# sequencer_uC.net
KiCad netlist of a schematic drawn in EAGLE
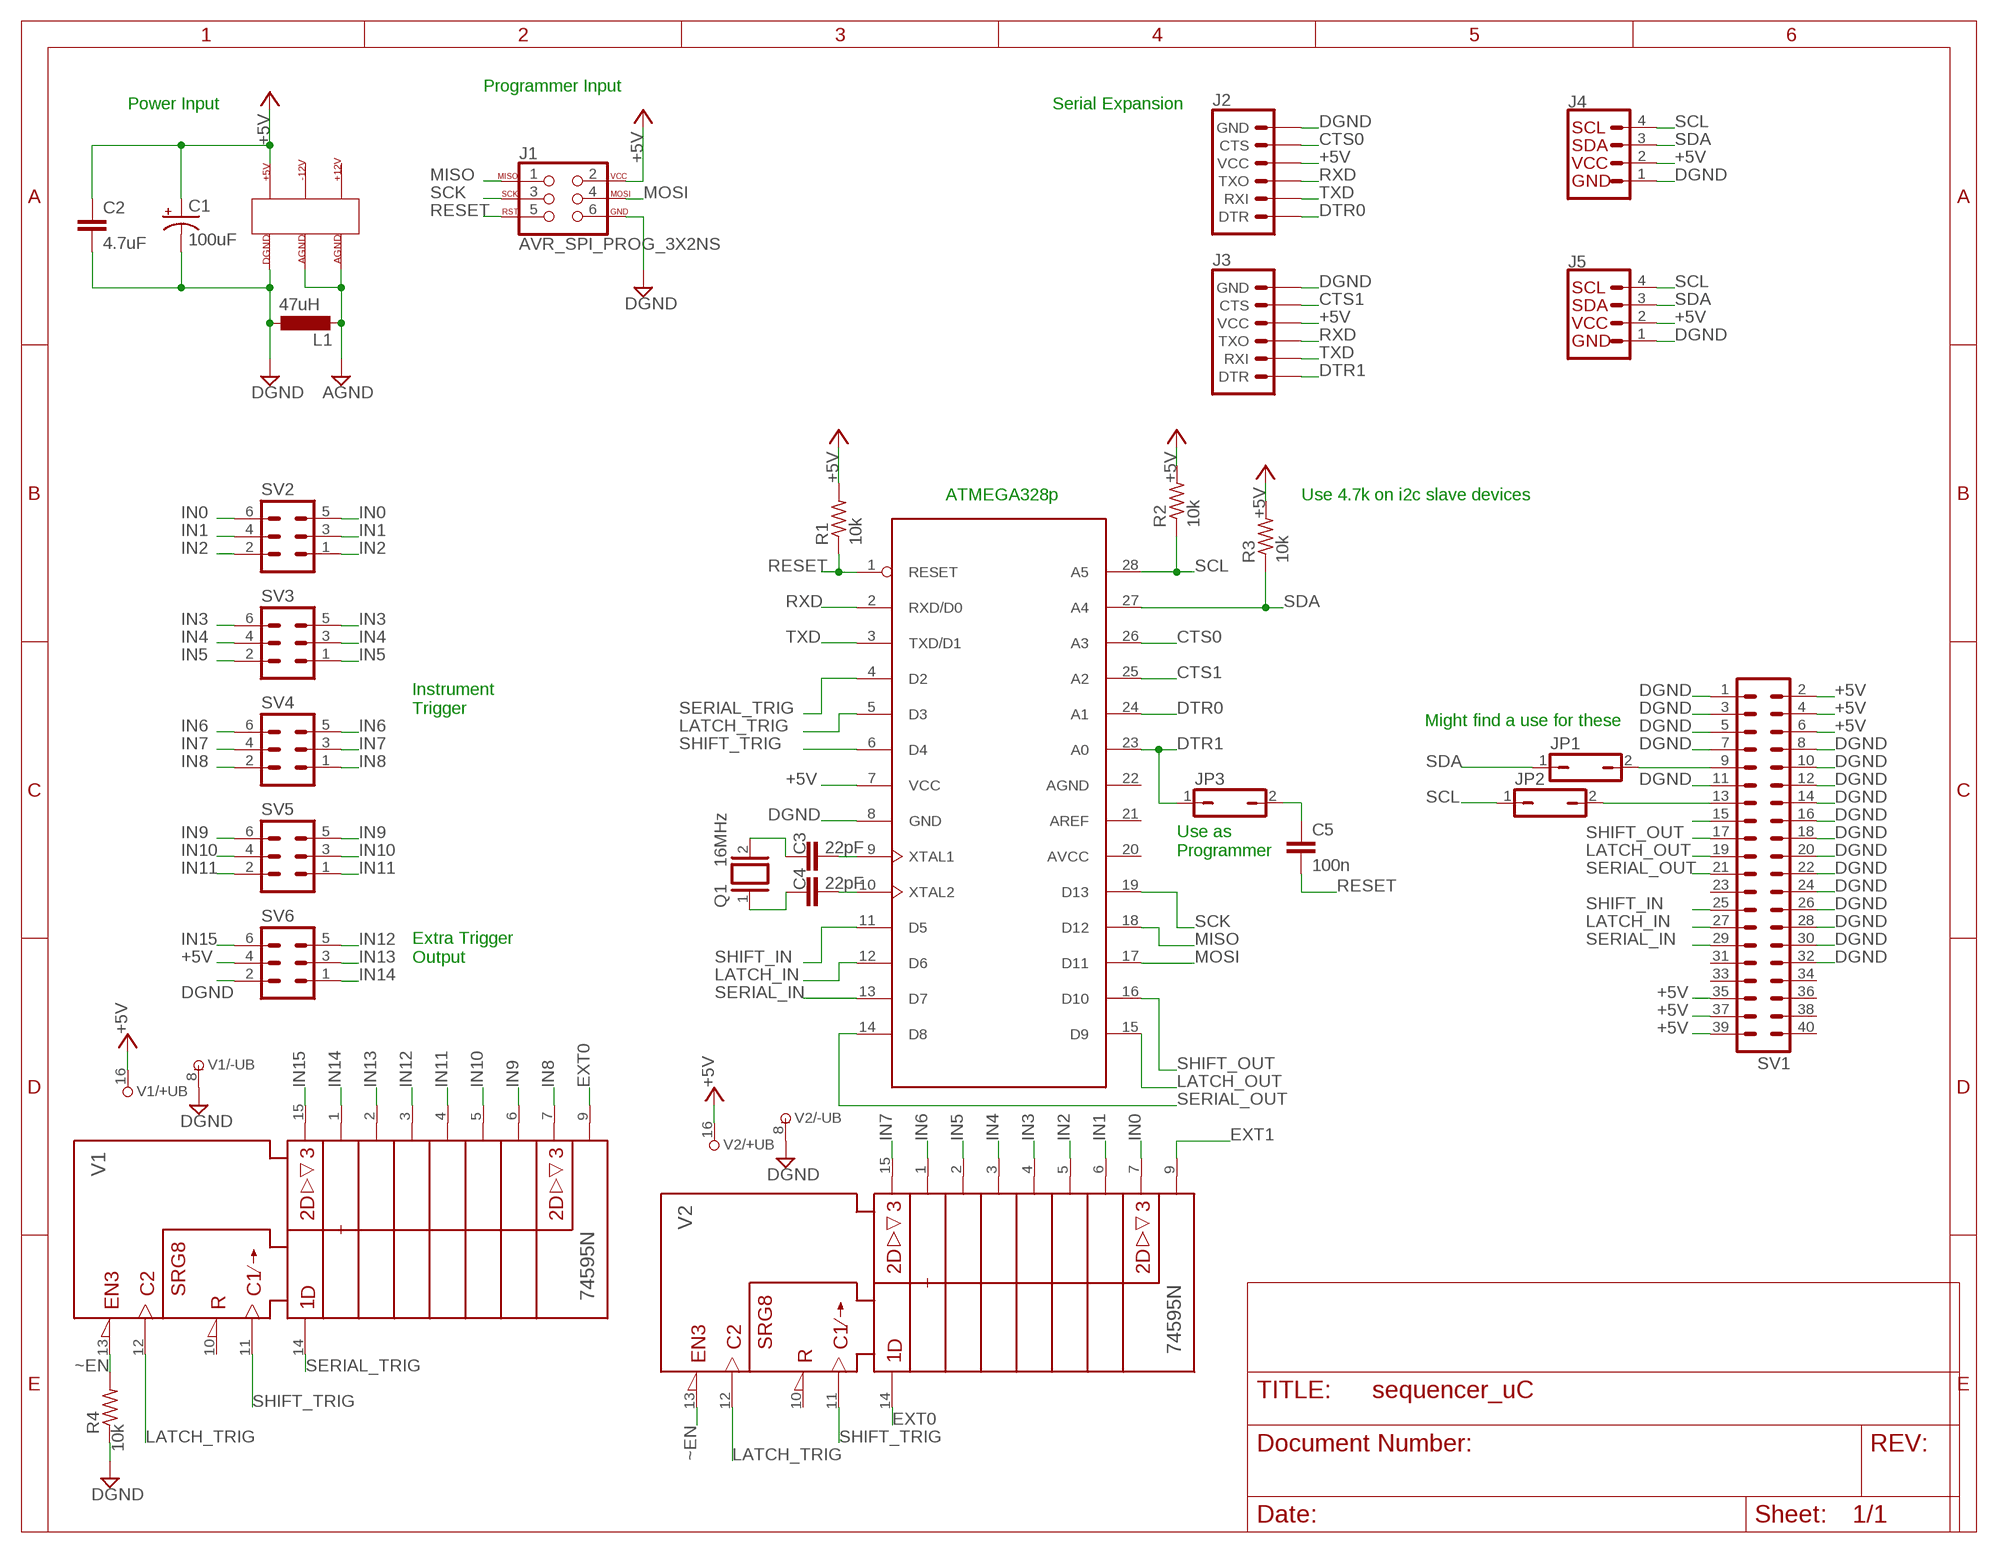
[diagram p0: schematic, sheet 1]

(export (version "E")
  (design (tool "Eeschema 10.0.6"))
  (components
    (comp (ref "AT1")
      (value "ATMEGA328")
      (footprint "eagle-import:DIP28-0.3IN")
      (libsource (lib "eagle-import") (part "ATMEGA328"))
    )
    (comp (ref "C1")
      (value "100uF")
      (footprint "eagle-import:E5-8,5")
      (libsource (lib "eagle-import") (part "CPOL-USE5-8.5"))
    )
    (comp (ref "C2")
      (value "4.7uF")
      (footprint "eagle-import:C050-024X044")
      (libsource (lib "eagle-import") (part "C-EU050-024X044"))
    )
    (comp (ref "C3")
      (value "22pF")
      (footprint "eagle-import:C050-024X044")
      (libsource (lib "eagle-import") (part "C-EU050-024X044"))
    )
    (comp (ref "C4")
      (value "22pF")
      (footprint "eagle-import:C050-024X044")
      (libsource (lib "eagle-import") (part "C-EU050-024X044"))
    )
    (comp (ref "C5")
      (value "100n")
      (footprint "eagle-import:C050-024X044")
      (libsource (lib "eagle-import") (part "C-EU050-024X044"))
    )
    (comp (ref "J1")
      (value "AVR_SPI_PROG_3X2NS")
      (footprint "eagle-import:2X3-NS")
      (libsource (lib "eagle-import") (part "AVR_SPI_PROG_3X2NS"))
    )
    (comp (ref "J2")
      (value "6_PIN_SERIAL_TARGETLONGPADS")
      (footprint "eagle-import:1X06_LONGPADS")
      (libsource (lib "eagle-import") (part "6_PIN_SERIAL_TARGETLONGPADS"))
    )
    (comp (ref "J3")
      (value "6_PIN_SERIAL_TARGETLONGPADS")
      (footprint "eagle-import:1X06_LONGPADS")
      (libsource (lib "eagle-import") (part "6_PIN_SERIAL_TARGETLONGPADS"))
    )
    (comp (ref "J4")
      (value "I2C_STANDARD")
      (footprint "eagle-import:1X04")
      (libsource (lib "eagle-import") (part "I2C_STANDARD"))
    )
    (comp (ref "J5")
      (value "I2C_STANDARD")
      (footprint "eagle-import:1X04")
      (libsource (lib "eagle-import") (part "I2C_STANDARD"))
    )
    (comp (ref "JP1")
      (value "JP1Q")
      (footprint "eagle-import:JP1")
      (libsource (lib "eagle-import") (part "JP1Q"))
    )
    (comp (ref "JP2")
      (value "JP1Q")
      (footprint "eagle-import:JP1")
      (libsource (lib "eagle-import") (part "JP1Q"))
    )
    (comp (ref "JP3")
      (value "JP1Q")
      (footprint "eagle-import:JP1")
      (libsource (lib "eagle-import") (part "JP1Q"))
    )
    (comp (ref "L1")
      (value "47uH")
      (footprint "eagle-import:0207_10")
      (libsource (lib "eagle-import") (part "L-EU0207/10"))
    )
    (comp (ref "Q1")
      (value "16MHz")
      (footprint "eagle-import:QS")
      (libsource (lib "eagle-import") (part "XTAL/S"))
    )
    (comp (ref "R1")
      (value "10k")
      (footprint "eagle-import:0204_7")
      (libsource (lib "eagle-import") (part "resistor_348_R-US_0204/7"))
    )
    (comp (ref "R2")
      (value "10k")
      (footprint "eagle-import:0204_7")
      (libsource (lib "eagle-import") (part "R-US_0204/7"))
    )
    (comp (ref "R3")
      (value "10k")
      (footprint "eagle-import:0204_7")
      (libsource (lib "eagle-import") (part "R-US_0204/7"))
    )
    (comp (ref "R4")
      (value "10k")
      (footprint "eagle-import:0204_7")
      (libsource (lib "eagle-import") (part "R-US_0204/7"))
    )
    (comp (ref "SV1")
      (value "MA20-2")
      (footprint "eagle-import:MA20-2")
      (libsource (lib "eagle-import") (part "MA20-2"))
    )
    (comp (ref "SV2")
      (value "MA03-2")
      (footprint "eagle-import:MA03-2")
      (libsource (lib "eagle-import") (part "MA03-2"))
    )
    (comp (ref "SV3")
      (value "MA03-2")
      (footprint "eagle-import:MA03-2")
      (libsource (lib "eagle-import") (part "MA03-2"))
    )
    (comp (ref "SV4")
      (value "MA03-2")
      (footprint "eagle-import:MA03-2")
      (libsource (lib "eagle-import") (part "MA03-2"))
    )
    (comp (ref "SV5")
      (value "MA03-2")
      (footprint "eagle-import:MA03-2")
      (libsource (lib "eagle-import") (part "MA03-2"))
    )
    (comp (ref "SV6")
      (value "MA03-2")
      (footprint "eagle-import:MA03-2")
      (libsource (lib "eagle-import") (part "MA03-2"))
    )
    (comp (ref "U$1")
      (value "TER6PIN_VERT")
      (footprint "eagle-import:CAPSTONE_1-770875-0")
      (libsource (lib "eagle-import") (part "TER6PIN_VERT"))
    )
    (comp (ref "V1")
      (value "74595N")
      (footprint "eagle-import:DIL16")
      (libsource (lib "eagle-import") (part "74595N"))
    )
    (comp (ref "V2")
      (value "74595N")
      (footprint "eagle-import:DIL16")
      (libsource (lib "eagle-import") (part "74595N"))
    )
  )
  (nets
    (net (code "1") (name "+5V") (class "Default")
      (node (ref "AT1") (pin "7") (pinfunction "VCC_7") (pintype "bidirectional"))
      (node (ref "C1") (pin "+") (pinfunction "+_+") (pintype "passive"))
      (node (ref "C2") (pin "1") (pinfunction "1_1") (pintype "passive"))
      (node (ref "J1") (pin "2") (pinfunction "2_2") (pintype "passive"))
      (node (ref "J2") (pin "4") (pinfunction "VCC_4") (pintype "passive"))
      (node (ref "J3") (pin "4") (pinfunction "VCC_4") (pintype "passive"))
      (node (ref "J4") (pin "2") (pinfunction "2_2") (pintype "power_in"))
      (node (ref "J5") (pin "2") (pinfunction "2_2") (pintype "power_in"))
      (node (ref "R1") (pin "2") (pinfunction "2_2") (pintype "passive"))
      (node (ref "R2") (pin "2") (pinfunction "2_2") (pintype "passive"))
      (node (ref "R3") (pin "2") (pinfunction "2_2") (pintype "passive"))
      (node (ref "SV1") (pin "2") (pinfunction "2_2") (pintype "passive"))
      (node (ref "SV1") (pin "35") (pinfunction "35_35") (pintype "passive"))
      (node (ref "SV1") (pin "37") (pinfunction "37_37") (pintype "passive"))
      (node (ref "SV1") (pin "39") (pinfunction "39_39") (pintype "passive"))
      (node (ref "SV1") (pin "4") (pinfunction "4_4") (pintype "passive"))
      (node (ref "SV1") (pin "6") (pinfunction "6_6") (pintype "passive"))
      (node (ref "SV6") (pin "4") (pinfunction "4_4") (pintype "passive"))
      (node (ref "U$1") (pin "+5V") (pinfunction "+5V_+5V") (pintype "bidirectional"))
      (node (ref "V1") (pin "16") (pinfunction "+UB_16") (pintype "power_in"))
      (node (ref "V2") (pin "16") (pinfunction "+UB_16") (pintype "power_in"))
    )
    (net (code "2") (name "/CTS0") (class "Default")
      (node (ref "AT1") (pin "26") (pinfunction "A3_26") (pintype "bidirectional"))
      (node (ref "J2") (pin "5") (pinfunction "CTS_5") (pintype "passive"))
    )
    (net (code "3") (name "/CTS1") (class "Default")
      (node (ref "AT1") (pin "25") (pinfunction "A2_25") (pintype "bidirectional"))
      (node (ref "J3") (pin "5") (pinfunction "CTS_5") (pintype "passive"))
    )
    (net (code "4") (name "/DTR0") (class "Default")
      (node (ref "AT1") (pin "24") (pinfunction "A1_24") (pintype "bidirectional"))
      (node (ref "J2") (pin "1") (pinfunction "DTR_1") (pintype "passive"))
    )
    (net (code "5") (name "/DTR1") (class "Default")
      (node (ref "AT1") (pin "23") (pinfunction "A0_23") (pintype "bidirectional"))
      (node (ref "J3") (pin "1") (pinfunction "DTR_1") (pintype "passive"))
      (node (ref "JP3") (pin "1") (pinfunction "1_1") (pintype "passive"))
    )
    (net (code "6") (name "/EXT0") (class "Default")
      (node (ref "V1") (pin "9") (pinfunction "QH*_9") (pintype "output"))
      (node (ref "V2") (pin "14") (pinfunction "SER_14") (pintype "input"))
    )
    (net (code "7") (name "/EXT1") (class "Default")
      (node (ref "V2") (pin "9") (pinfunction "QH*_9") (pintype "output"))
    )
    (net (code "8") (name "/IN0") (class "Default")
      (node (ref "SV2") (pin "5") (pinfunction "5_5") (pintype "passive"))
      (node (ref "SV2") (pin "6") (pinfunction "6_6") (pintype "passive"))
      (node (ref "V2") (pin "7") (pinfunction "QH_7") (pintype "tri_state"))
    )
    (net (code "9") (name "/IN1") (class "Default")
      (node (ref "SV2") (pin "3") (pinfunction "3_3") (pintype "passive"))
      (node (ref "SV2") (pin "4") (pinfunction "4_4") (pintype "passive"))
      (node (ref "V2") (pin "6") (pinfunction "QG_6") (pintype "tri_state"))
    )
    (net (code "10") (name "/IN2") (class "Default")
      (node (ref "SV2") (pin "1") (pinfunction "1_1") (pintype "passive"))
      (node (ref "SV2") (pin "2") (pinfunction "2_2") (pintype "passive"))
      (node (ref "V2") (pin "5") (pinfunction "QF_5") (pintype "tri_state"))
    )
    (net (code "11") (name "/IN3") (class "Default")
      (node (ref "SV3") (pin "5") (pinfunction "5_5") (pintype "passive"))
      (node (ref "SV3") (pin "6") (pinfunction "6_6") (pintype "passive"))
      (node (ref "V2") (pin "4") (pinfunction "QE_4") (pintype "tri_state"))
    )
    (net (code "12") (name "/IN4") (class "Default")
      (node (ref "SV3") (pin "3") (pinfunction "3_3") (pintype "passive"))
      (node (ref "SV3") (pin "4") (pinfunction "4_4") (pintype "passive"))
      (node (ref "V2") (pin "3") (pinfunction "QD_3") (pintype "tri_state"))
    )
    (net (code "13") (name "/IN5") (class "Default")
      (node (ref "SV3") (pin "1") (pinfunction "1_1") (pintype "passive"))
      (node (ref "SV3") (pin "2") (pinfunction "2_2") (pintype "passive"))
      (node (ref "V2") (pin "2") (pinfunction "QC_2") (pintype "tri_state"))
    )
    (net (code "14") (name "/IN6") (class "Default")
      (node (ref "SV4") (pin "5") (pinfunction "5_5") (pintype "passive"))
      (node (ref "SV4") (pin "6") (pinfunction "6_6") (pintype "passive"))
      (node (ref "V2") (pin "1") (pinfunction "QB_1") (pintype "tri_state"))
    )
    (net (code "15") (name "/IN7") (class "Default")
      (node (ref "SV4") (pin "3") (pinfunction "3_3") (pintype "passive"))
      (node (ref "SV4") (pin "4") (pinfunction "4_4") (pintype "passive"))
      (node (ref "V2") (pin "15") (pinfunction "QA_15") (pintype "tri_state"))
    )
    (net (code "16") (name "/IN8") (class "Default")
      (node (ref "SV4") (pin "1") (pinfunction "1_1") (pintype "passive"))
      (node (ref "SV4") (pin "2") (pinfunction "2_2") (pintype "passive"))
      (node (ref "V1") (pin "7") (pinfunction "QH_7") (pintype "tri_state"))
    )
    (net (code "17") (name "/IN9") (class "Default")
      (node (ref "SV5") (pin "5") (pinfunction "5_5") (pintype "passive"))
      (node (ref "SV5") (pin "6") (pinfunction "6_6") (pintype "passive"))
      (node (ref "V1") (pin "6") (pinfunction "QG_6") (pintype "tri_state"))
    )
    (net (code "18") (name "/IN10") (class "Default")
      (node (ref "SV5") (pin "3") (pinfunction "3_3") (pintype "passive"))
      (node (ref "SV5") (pin "4") (pinfunction "4_4") (pintype "passive"))
      (node (ref "V1") (pin "5") (pinfunction "QF_5") (pintype "tri_state"))
    )
    (net (code "19") (name "/IN11") (class "Default")
      (node (ref "SV5") (pin "1") (pinfunction "1_1") (pintype "passive"))
      (node (ref "SV5") (pin "2") (pinfunction "2_2") (pintype "passive"))
      (node (ref "V1") (pin "4") (pinfunction "QE_4") (pintype "tri_state"))
    )
    (net (code "20") (name "/IN12") (class "Default")
      (node (ref "SV6") (pin "5") (pinfunction "5_5") (pintype "passive"))
      (node (ref "V1") (pin "3") (pinfunction "QD_3") (pintype "tri_state"))
    )
    (net (code "21") (name "/IN13") (class "Default")
      (node (ref "SV6") (pin "3") (pinfunction "3_3") (pintype "passive"))
      (node (ref "V1") (pin "2") (pinfunction "QC_2") (pintype "tri_state"))
    )
    (net (code "22") (name "/IN14") (class "Default")
      (node (ref "SV6") (pin "1") (pinfunction "1_1") (pintype "passive"))
      (node (ref "V1") (pin "1") (pinfunction "QB_1") (pintype "tri_state"))
    )
    (net (code "23") (name "/IN15") (class "Default")
      (node (ref "SV6") (pin "6") (pinfunction "6_6") (pintype "passive"))
      (node (ref "V1") (pin "15") (pinfunction "QA_15") (pintype "tri_state"))
    )
    (net (code "24") (name "/LATCH_IN") (class "Default")
      (node (ref "AT1") (pin "12") (pinfunction "D6_12") (pintype "bidirectional"))
      (node (ref "SV1") (pin "27") (pinfunction "27_27") (pintype "passive"))
    )
    (net (code "25") (name "/LATCH_OUT") (class "Default")
      (node (ref "AT1") (pin "15") (pinfunction "D9_15") (pintype "bidirectional"))
      (node (ref "SV1") (pin "19") (pinfunction "19_19") (pintype "passive"))
    )
    (net (code "26") (name "/LATCH_TRIG") (class "Default")
      (node (ref "AT1") (pin "5") (pinfunction "D3_5") (pintype "bidirectional"))
      (node (ref "V1") (pin "12") (pinfunction "RCK_12") (pintype "input"))
      (node (ref "V2") (pin "12") (pinfunction "RCK_12") (pintype "input"))
    )
    (net (code "27") (name "/MISO") (class "Default")
      (node (ref "AT1") (pin "18") (pinfunction "D12_18") (pintype "bidirectional"))
      (node (ref "J1") (pin "1") (pinfunction "1_1") (pintype "passive"))
    )
    (net (code "28") (name "/MOSI") (class "Default")
      (node (ref "AT1") (pin "17") (pinfunction "D11_17") (pintype "bidirectional"))
      (node (ref "J1") (pin "4") (pinfunction "4_4") (pintype "passive"))
    )
    (net (code "29") (name "/RESET") (class "Default")
      (node (ref "AT1") (pin "1") (pinfunction "RESET_1") (pintype "bidirectional"))
      (node (ref "C5") (pin "2") (pinfunction "2_2") (pintype "passive"))
      (node (ref "J1") (pin "5") (pinfunction "5_5") (pintype "passive"))
      (node (ref "R1") (pin "1") (pinfunction "1_1") (pintype "passive"))
    )
    (net (code "30") (name "/RXD") (class "Default")
      (node (ref "AT1") (pin "2") (pinfunction "RXD/D0_2") (pintype "bidirectional"))
      (node (ref "J2") (pin "3") (pinfunction "TXO_3") (pintype "passive"))
      (node (ref "J3") (pin "3") (pinfunction "TXO_3") (pintype "passive"))
    )
    (net (code "31") (name "/SCK") (class "Default")
      (node (ref "AT1") (pin "19") (pinfunction "D13_19") (pintype "bidirectional"))
      (node (ref "J1") (pin "3") (pinfunction "3_3") (pintype "passive"))
    )
    (net (code "32") (name "/SCL") (class "Default")
      (node (ref "AT1") (pin "28") (pinfunction "A5_28") (pintype "bidirectional"))
      (node (ref "J4") (pin "4") (pinfunction "4_4") (pintype "passive"))
      (node (ref "J5") (pin "4") (pinfunction "4_4") (pintype "passive"))
      (node (ref "JP2") (pin "1") (pinfunction "1_1") (pintype "passive"))
      (node (ref "R2") (pin "1") (pinfunction "1_1") (pintype "passive"))
    )
    (net (code "33") (name "/SDA") (class "Default")
      (node (ref "AT1") (pin "27") (pinfunction "A4_27") (pintype "bidirectional"))
      (node (ref "J4") (pin "3") (pinfunction "3_3") (pintype "passive"))
      (node (ref "J5") (pin "3") (pinfunction "3_3") (pintype "passive"))
      (node (ref "JP1") (pin "1") (pinfunction "1_1") (pintype "passive"))
      (node (ref "R3") (pin "1") (pinfunction "1_1") (pintype "passive"))
    )
    (net (code "34") (name "/SERIAL_IN") (class "Default")
      (node (ref "AT1") (pin "13") (pinfunction "D7_13") (pintype "bidirectional"))
      (node (ref "SV1") (pin "29") (pinfunction "29_29") (pintype "passive"))
    )
    (net (code "35") (name "/SERIAL_OUT") (class "Default")
      (node (ref "AT1") (pin "14") (pinfunction "D8_14") (pintype "bidirectional"))
      (node (ref "SV1") (pin "21") (pinfunction "21_21") (pintype "passive"))
    )
    (net (code "36") (name "/SERIAL_TRIG") (class "Default")
      (node (ref "AT1") (pin "4") (pinfunction "D2_4") (pintype "bidirectional"))
      (node (ref "V1") (pin "14") (pinfunction "SER_14") (pintype "input"))
    )
    (net (code "37") (name "/SHIFT_IN") (class "Default")
      (node (ref "AT1") (pin "11") (pinfunction "D5_11") (pintype "bidirectional"))
      (node (ref "SV1") (pin "25") (pinfunction "25_25") (pintype "passive"))
    )
    (net (code "38") (name "/SHIFT_OUT") (class "Default")
      (node (ref "AT1") (pin "16") (pinfunction "D10_16") (pintype "bidirectional"))
      (node (ref "SV1") (pin "17") (pinfunction "17_17") (pintype "passive"))
    )
    (net (code "39") (name "/SHIFT_TRIG") (class "Default")
      (node (ref "AT1") (pin "6") (pinfunction "D4_6") (pintype "bidirectional"))
      (node (ref "V1") (pin "11") (pinfunction "SRCK_11") (pintype "input"))
      (node (ref "V2") (pin "11") (pinfunction "SRCK_11") (pintype "input"))
    )
    (net (code "40") (name "/TXD") (class "Default")
      (node (ref "AT1") (pin "3") (pinfunction "TXD/D1_3") (pintype "bidirectional"))
      (node (ref "J2") (pin "2") (pinfunction "RXI_2") (pintype "passive"))
      (node (ref "J3") (pin "2") (pinfunction "RXI_2") (pintype "passive"))
    )
    (net (code "41") (name "/~{EN}") (class "Default")
      (node (ref "R4") (pin "2") (pinfunction "2_2") (pintype "passive"))
      (node (ref "V1") (pin "13") (pinfunction "~{G}_13") (pintype "input"))
      (node (ref "V2") (pin "13") (pinfunction "~{G}_13") (pintype "input"))
    )
    (net (code "42") (name "AGND") (class "Default")
      (node (ref "L1") (pin "2") (pinfunction "2_2") (pintype "passive"))
      (node (ref "U$1") (pin "AGND0") (pinfunction "AGND0_AGND0") (pintype "bidirectional"))
      (node (ref "U$1") (pin "AGND1") (pinfunction "AGND1_AGND1") (pintype "bidirectional"))
    )
    (net (code "43") (name "DGND") (class "Default")
      (node (ref "AT1") (pin "8") (pinfunction "GND_8") (pintype "bidirectional"))
      (node (ref "C1") (pin "-") (pinfunction "-_-") (pintype "passive"))
      (node (ref "C2") (pin "2") (pinfunction "2_2") (pintype "passive"))
      (node (ref "J1") (pin "6") (pinfunction "6_6") (pintype "passive"))
      (node (ref "J2") (pin "6") (pinfunction "GND_6") (pintype "passive"))
      (node (ref "J3") (pin "6") (pinfunction "GND_6") (pintype "passive"))
      (node (ref "J4") (pin "1") (pinfunction "1_1") (pintype "power_in"))
      (node (ref "J5") (pin "1") (pinfunction "1_1") (pintype "power_in"))
      (node (ref "L1") (pin "1") (pinfunction "1_1") (pintype "passive"))
      (node (ref "R4") (pin "1") (pinfunction "1_1") (pintype "passive"))
      (node (ref "SV1") (pin "1") (pinfunction "1_1") (pintype "passive"))
      (node (ref "SV1") (pin "10") (pinfunction "10_10") (pintype "passive"))
      (node (ref "SV1") (pin "11") (pinfunction "11_11") (pintype "passive"))
      (node (ref "SV1") (pin "12") (pinfunction "12_12") (pintype "passive"))
      (node (ref "SV1") (pin "14") (pinfunction "14_14") (pintype "passive"))
      (node (ref "SV1") (pin "15") (pinfunction "15_15") (pintype "passive"))
      (node (ref "SV1") (pin "16") (pinfunction "16_16") (pintype "passive"))
      (node (ref "SV1") (pin "18") (pinfunction "18_18") (pintype "passive"))
      (node (ref "SV1") (pin "20") (pinfunction "20_20") (pintype "passive"))
      (node (ref "SV1") (pin "22") (pinfunction "22_22") (pintype "passive"))
      (node (ref "SV1") (pin "24") (pinfunction "24_24") (pintype "passive"))
      (node (ref "SV1") (pin "26") (pinfunction "26_26") (pintype "passive"))
      (node (ref "SV1") (pin "28") (pinfunction "28_28") (pintype "passive"))
      (node (ref "SV1") (pin "3") (pinfunction "3_3") (pintype "passive"))
      (node (ref "SV1") (pin "30") (pinfunction "30_30") (pintype "passive"))
      (node (ref "SV1") (pin "32") (pinfunction "32_32") (pintype "passive"))
      (node (ref "SV1") (pin "5") (pinfunction "5_5") (pintype "passive"))
      (node (ref "SV1") (pin "7") (pinfunction "7_7") (pintype "passive"))
      (node (ref "SV1") (pin "8") (pinfunction "8_8") (pintype "passive"))
      (node (ref "SV6") (pin "2") (pinfunction "2_2") (pintype "passive"))
      (node (ref "U$1") (pin "DGND") (pinfunction "DGND_DGND") (pintype "bidirectional"))
      (node (ref "U$1") (pin "NULL") (pinfunction "DGND_NULL") (pintype "bidirectional"))
      (node (ref "V1") (pin "8") (pinfunction "-UB_8") (pintype "power_in"))
      (node (ref "V2") (pin "8") (pinfunction "-UB_8") (pintype "power_in"))
    )
    (net (code "44") (name "Net-(AT1-XTAL1)") (class "Default")
      (node (ref "AT1") (pin "9") (pinfunction "XTAL1_9") (pintype "bidirectional"))
      (node (ref "C3") (pin "2") (pinfunction "2_2") (pintype "passive"))
    )
    (net (code "45") (name "Net-(AT1-XTAL2)") (class "Default")
      (node (ref "AT1") (pin "10") (pinfunction "XTAL2_10") (pintype "bidirectional"))
      (node (ref "C4") (pin "2") (pinfunction "2_2") (pintype "passive"))
    )
    (net (code "46") (name "Net-(C3-Pad1)") (class "Default")
      (node (ref "C3") (pin "1") (pinfunction "1_1") (pintype "passive"))
      (node (ref "Q1") (pin "2") (pinfunction "2_2") (pintype "passive"))
    )
    (net (code "47") (name "Net-(C4-Pad1)") (class "Default")
      (node (ref "C4") (pin "1") (pinfunction "1_1") (pintype "passive"))
      (node (ref "Q1") (pin "1") (pinfunction "1_1") (pintype "passive"))
    )
    (net (code "48") (name "Net-(C5-Pad1)") (class "Default")
      (node (ref "C5") (pin "1") (pinfunction "1_1") (pintype "passive"))
      (node (ref "JP3") (pin "2") (pinfunction "2_2") (pintype "passive"))
    )
    (net (code "49") (name "Net-(JP1-Pad2)") (class "Default")
      (node (ref "JP1") (pin "2") (pinfunction "2_2") (pintype "passive"))
      (node (ref "SV1") (pin "9") (pinfunction "9_9") (pintype "passive"))
    )
    (net (code "50") (name "Net-(JP2-Pad2)") (class "Default")
      (node (ref "JP2") (pin "2") (pinfunction "2_2") (pintype "passive"))
      (node (ref "SV1") (pin "13") (pinfunction "13_13") (pintype "passive"))
    )
    (net (code "51") (name "unconnected-(AT1-AGND-Pad22)") (class "Default")
      (node (ref "AT1") (pin "22") (pinfunction "AGND_22") (pintype "bidirectional"))
    )
    (net (code "52") (name "unconnected-(AT1-AREF-Pad21)") (class "Default")
      (node (ref "AT1") (pin "21") (pinfunction "AREF_21") (pintype "bidirectional"))
    )
    (net (code "53") (name "unconnected-(AT1-AVCC-Pad20)") (class "Default")
      (node (ref "AT1") (pin "20") (pinfunction "AVCC_20") (pintype "bidirectional"))
    )
    (net (code "54") (name "unconnected-(SV1-Pad23)") (class "Default")
      (node (ref "SV1") (pin "23") (pinfunction "23_23") (pintype "passive"))
    )
    (net (code "55") (name "unconnected-(SV1-Pad31)") (class "Default")
      (node (ref "SV1") (pin "31") (pinfunction "31_31") (pintype "passive"))
    )
    (net (code "56") (name "unconnected-(SV1-Pad33)") (class "Default")
      (node (ref "SV1") (pin "33") (pinfunction "33_33") (pintype "passive"))
    )
    (net (code "57") (name "unconnected-(SV1-Pad34)") (class "Default")
      (node (ref "SV1") (pin "34") (pinfunction "34_34") (pintype "passive"))
    )
    (net (code "58") (name "unconnected-(SV1-Pad36)") (class "Default")
      (node (ref "SV1") (pin "36") (pinfunction "36_36") (pintype "passive"))
    )
    (net (code "59") (name "unconnected-(SV1-Pad38)") (class "Default")
      (node (ref "SV1") (pin "38") (pinfunction "38_38") (pintype "passive"))
    )
    (net (code "60") (name "unconnected-(SV1-Pad40)") (class "Default")
      (node (ref "SV1") (pin "40") (pinfunction "40_40") (pintype "passive"))
    )
    (net (code "61") (name "unconnected-(U$1-Pad+12V)") (class "Default")
      (node (ref "U$1") (pin "+12V") (pinfunction "+12V_+12V") (pintype "bidirectional"))
    )
    (net (code "62") (name "unconnected-(U$1-Pad-12V)") (class "Default")
      (node (ref "U$1") (pin "-12V") (pinfunction "-12V_-12V") (pintype "bidirectional"))
    )
    (net (code "63") (name "unconnected-(V1C-~{SRCLR}-Pad10)") (class "Default")
      (node (ref "V1") (pin "10") (pinfunction "~{SRCLR}_10") (pintype "input"))
    )
    (net (code "64") (name "unconnected-(V2C-~{SRCLR}-Pad10)") (class "Default")
      (node (ref "V2") (pin "10") (pinfunction "~{SRCLR}_10") (pintype "input"))
    )
  )
)
